# LED-Test-Board_v13.net
KiCad netlist of a schematic drawn in EAGLE
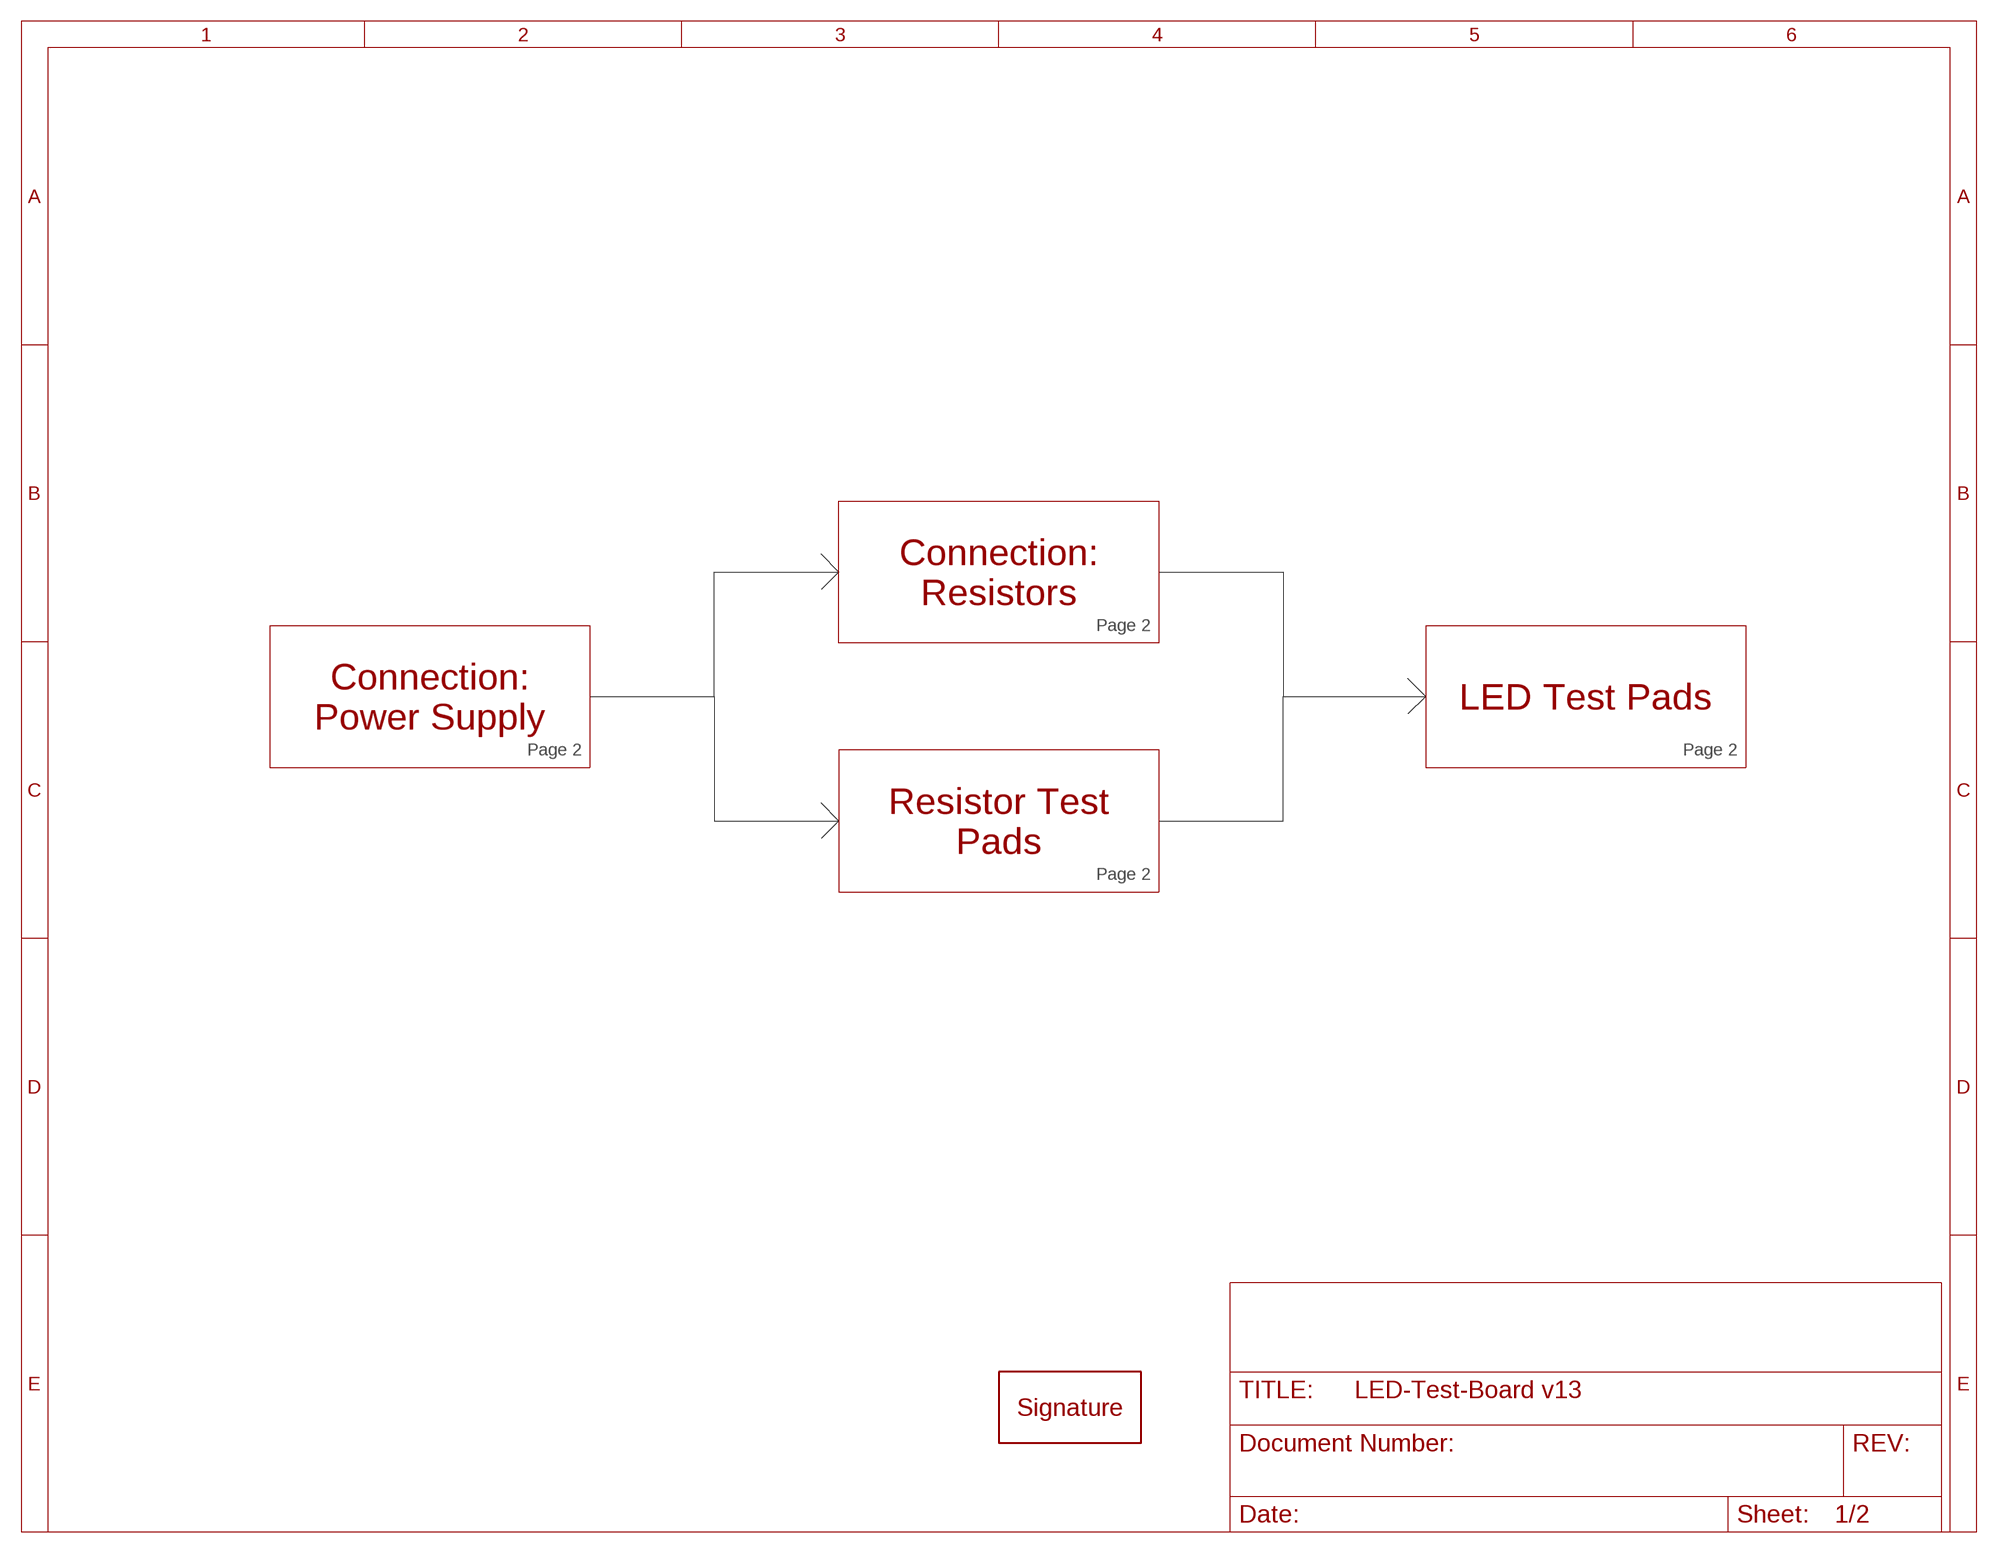
[diagram p0: schematic, sheet 1]
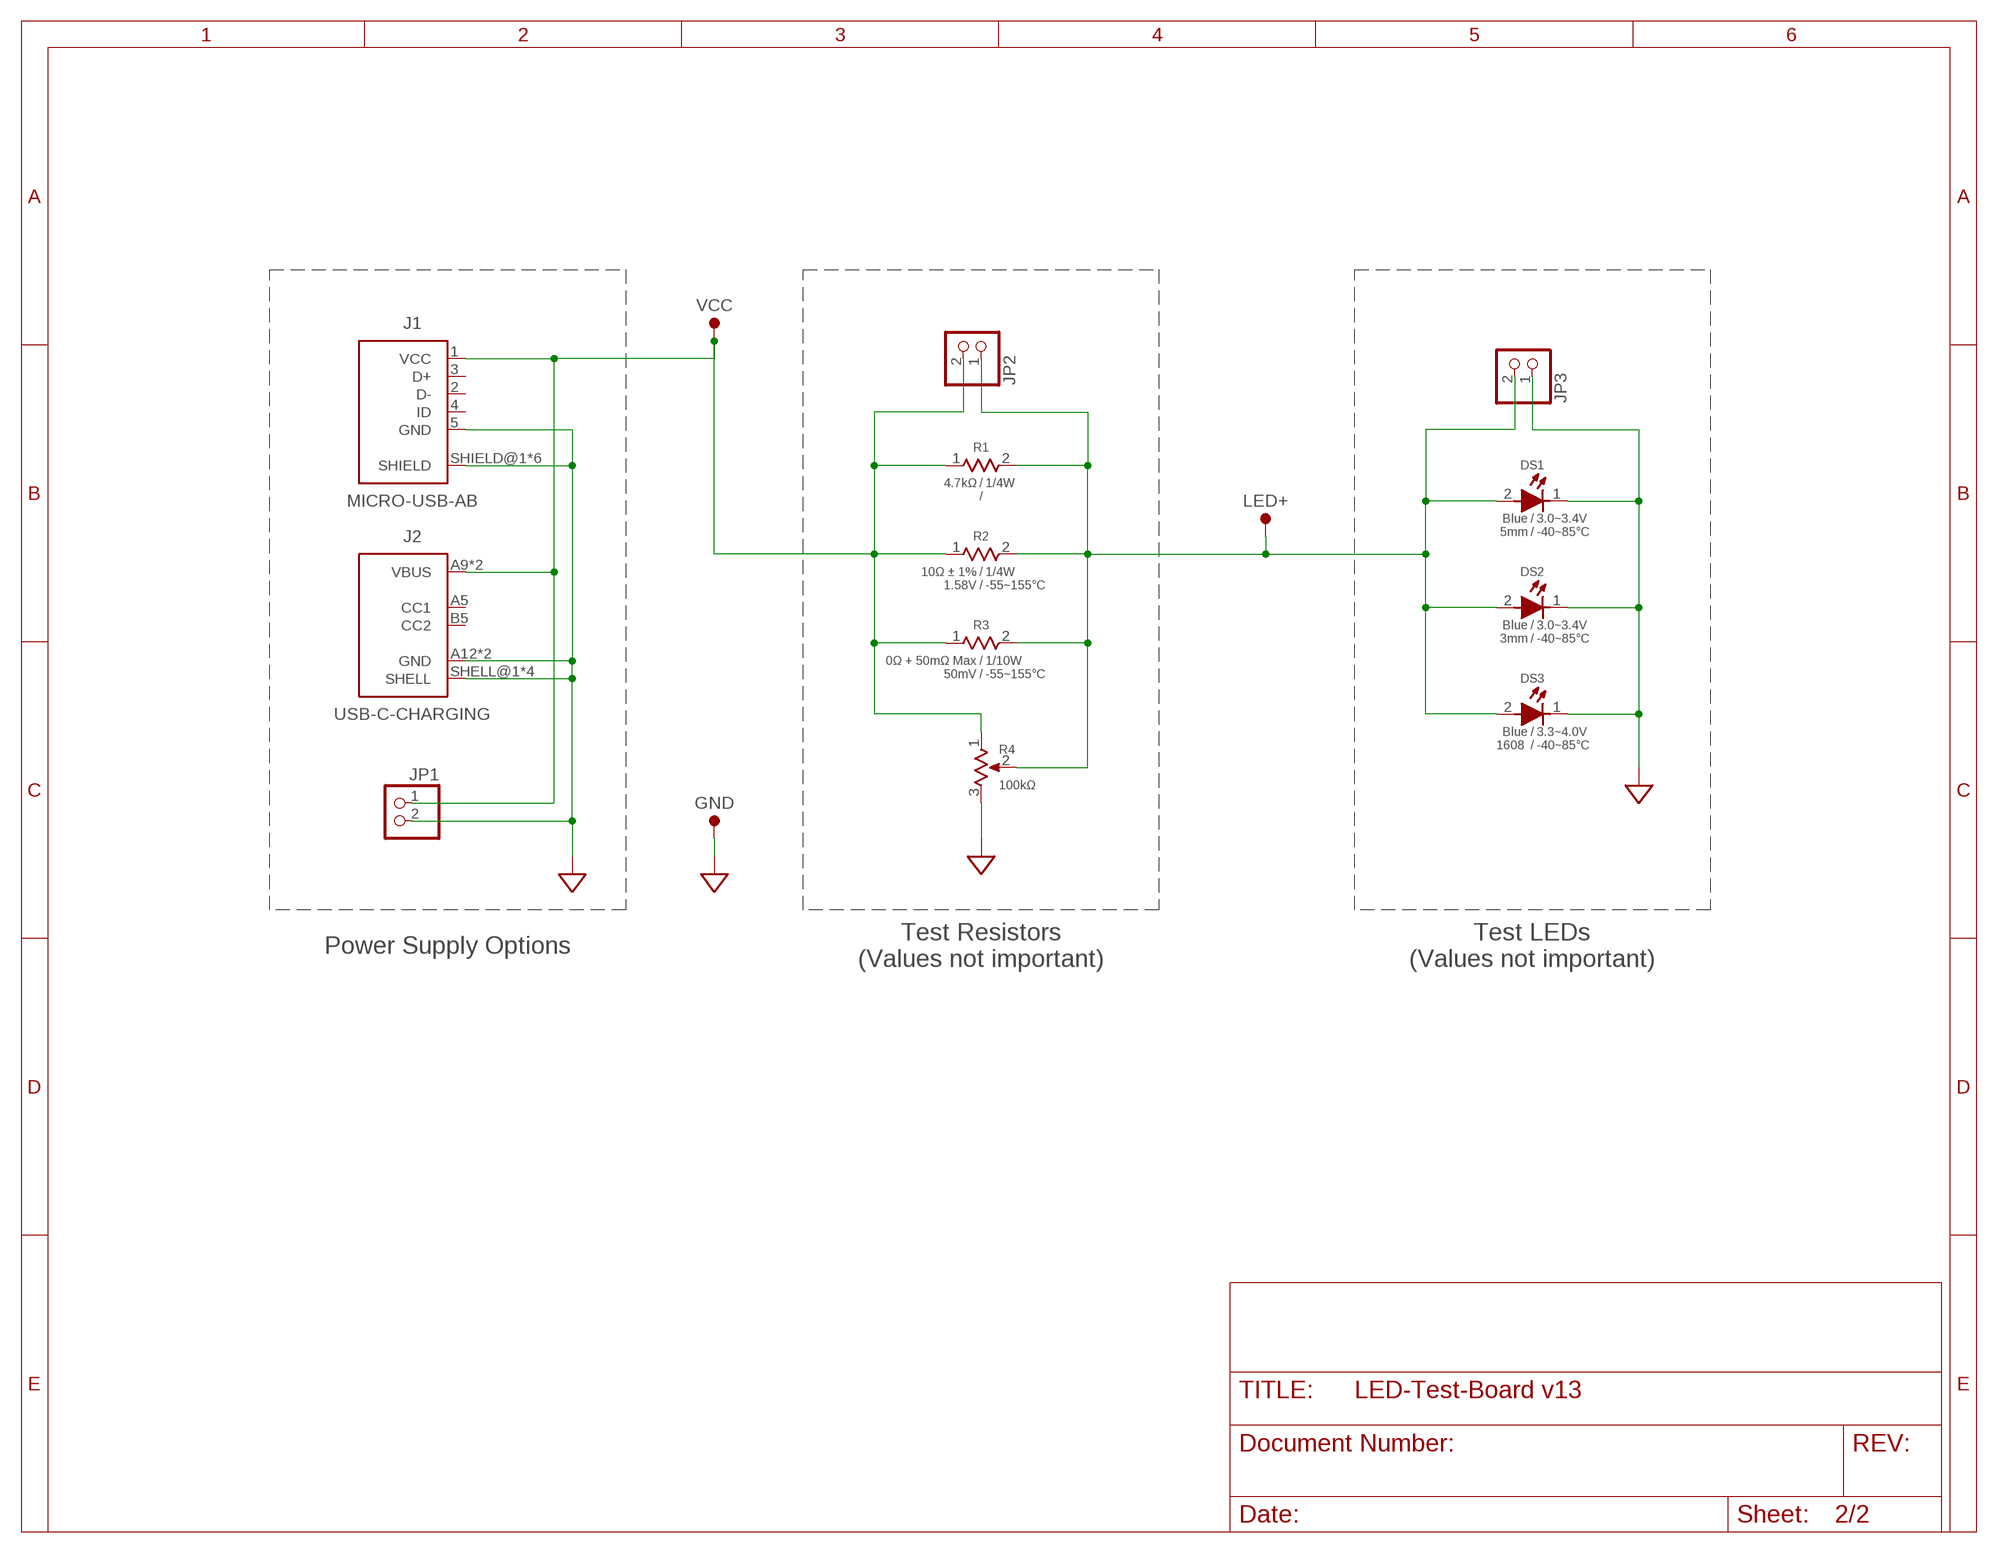
[diagram p1: schematic, sheet 2]

(export (version "E")
  (design (tool "Eeschema 10.0.6"))
  (components
    (comp (ref "DS1")
      (value "Blue")
      (footprint "eagle-import:5MM-TH")
      (fields
        (field (name "SIZE") "5mm")
        (field (name "TEMPERATURE") "-40~85°C")
        (field (name "VOLTAGE") "3.0~3.4V")
      )
      (libsource (lib "eagle-import") (part "LED-H-5MM-TH-BLUE"))
    )
    (comp (ref "DS2")
      (value "Blue")
      (footprint "eagle-import:3MM-TH")
      (fields
        (field (name "SIZE") "3mm")
        (field (name "TEMPERATURE") "-40~85°C")
        (field (name "VOLTAGE") "3.0~3.4V")
      )
      (libsource (lib "eagle-import") (part "LED-H-3MM-TH-BLUE"))
    )
    (comp (ref "DS3")
      (value "Blue")
      (footprint "eagle-import:1608")
      (fields
        (field (name "SIZE") "1608 ")
        (field (name "TEMPERATURE") "-40~85°C")
        (field (name "VOLTAGE") "3.3~4.0V")
      )
      (libsource (lib "eagle-import") (part "LED-H-1608-BLUE"))
    )
    (comp (ref "GND")
      (value "TEST-POINT")
      (footprint "eagle-import:TEST-POINT")
      (libsource (lib "eagle-import") (part "TEST-POINT"))
    )
    (comp (ref "J1")
      (value "MICRO-USB-AB")
      (footprint "eagle-import:47589-0001")
      (libsource (lib "eagle-import") (part "MICRO-USB-AB"))
    )
    (comp (ref "J2")
      (value "USB-C-CHARGING")
      (footprint "eagle-import:USB-4125")
      (libsource (lib "eagle-import") (part "USB-C-CHARGING"))
    )
    (comp (ref "JP1")
      (value "PINHD-1X2")
      (footprint "eagle-import:1X02")
      (libsource (lib "eagle-import") (part "PINHD-1X2"))
    )
    (comp (ref "JP2")
      (value "PINHD-1X2")
      (footprint "eagle-import:1X02")
      (libsource (lib "eagle-import") (part "PINHD-1X2"))
    )
    (comp (ref "JP3")
      (value "PINHD-1X2")
      (footprint "eagle-import:1X02")
      (libsource (lib "eagle-import") (part "PINHD-1X2"))
    )
    (comp (ref "LED+")
      (value "TEST-POINT")
      (footprint "eagle-import:TEST-POINT")
      (libsource (lib "eagle-import") (part "TEST-POINT"))
    )
    (comp (ref "R1")
      (value "4.7kΩ")
      (footprint "eagle-import:1_4W-TH")
      (fields (field (name "POWER") "1/4W"))
      (libsource (lib "eagle-import") (part "RES-H1/4W-TH"))
    )
    (comp (ref "R2")
      (value "10Ω ± 1%")
      (footprint "eagle-import:3216-SEM")
      (fields
        (field (name "POWER") "1/4W")
        (field (name "TEMPERATURE") "-55~155°C")
        (field (name "VOLTAGE") "1.58V")
      )
      (libsource (lib "eagle-import") (part "RES-H-3216-10R"))
    )
    (comp (ref "R3")
      (value "0Ω + 50mΩ Max")
      (footprint "eagle-import:1608-SEM")
      (fields
        (field (name "POWER") "1/10W")
        (field (name "TEMPERATURE") "-55~155°C")
        (field (name "VOLTAGE") "50mV")
      )
      (libsource (lib "eagle-import") (part "RES-H-1608-0R"))
    )
    (comp (ref "R4")
      (value "100kΩ")
      (footprint "eagle-import:3314J")
      (libsource (lib "eagle-import") (part "TRIMPOT-V-100K"))
    )
    (comp (ref "VCC")
      (value "TEST-POINT")
      (footprint "eagle-import:TEST-POINT")
      (libsource (lib "eagle-import") (part "TEST-POINT"))
    )
    (comp (ref "U$5")
      (value "SIGNATURE")
      (footprint "eagle-import:SIGNATURE")
      (libsource (lib "eagle-import") (part "SIGNATURE"))
    )
  )
  (nets
    (net (code "1") (name "GND") (class "Default")
      (node (ref "DS1") (pin "1") (pinfunction "1_1") (pintype "output"))
      (node (ref "DS2") (pin "1") (pinfunction "1_1") (pintype "output"))
      (node (ref "DS3") (pin "1") (pinfunction "1_1") (pintype "output"))
      (node (ref "GND") (pin "TP") (pinfunction "TP_TP") (pintype "bidirectional"))
      (node (ref "J1") (pin "5") (pinfunction "GND_5") (pintype "power_in"))
      (node (ref "J1") (pin "SHIELD@1") (pinfunction "SHIELD_SHIELD@1") (pintype "power_in"))
      (node (ref "J1") (pin "SHIELD@2") (pinfunction "SHIELD_SHIELD@2") (pintype "power_in"))
      (node (ref "J1") (pin "SHIELD@3") (pinfunction "SHIELD_SHIELD@3") (pintype "power_in"))
      (node (ref "J1") (pin "SHIELD@4") (pinfunction "SHIELD_SHIELD@4") (pintype "power_in"))
      (node (ref "J1") (pin "SHIELD@5") (pinfunction "SHIELD_SHIELD@5") (pintype "power_in"))
      (node (ref "J1") (pin "SHIELD@6") (pinfunction "SHIELD_SHIELD@6") (pintype "power_in"))
      (node (ref "J2") (pin "A12") (pinfunction "GND_A12") (pintype "power_in"))
      (node (ref "J2") (pin "B12") (pinfunction "GND_B12") (pintype "power_in"))
      (node (ref "J2") (pin "SHELL@1") (pinfunction "SHELL_SHELL@1") (pintype "power_in"))
      (node (ref "J2") (pin "SHELL@2") (pinfunction "SHELL_SHELL@2") (pintype "power_in"))
      (node (ref "J2") (pin "SHELL@3") (pinfunction "SHELL_SHELL@3") (pintype "power_in"))
      (node (ref "J2") (pin "SHELL@4") (pinfunction "SHELL_SHELL@4") (pintype "power_in"))
      (node (ref "JP1") (pin "2") (pinfunction "2_2") (pintype "passive"))
      (node (ref "JP3") (pin "1") (pinfunction "1_1") (pintype "passive"))
      (node (ref "R4") (pin "3") (pinfunction "3_3") (pintype "passive"))
    )
    (net (code "2") (name "Net-(DS1-Pad2)") (class "Default")
      (node (ref "DS1") (pin "2") (pinfunction "2_2") (pintype "input"))
      (node (ref "DS2") (pin "2") (pinfunction "2_2") (pintype "input"))
      (node (ref "DS3") (pin "2") (pinfunction "2_2") (pintype "input"))
      (node (ref "JP2") (pin "1") (pinfunction "1_1") (pintype "passive"))
      (node (ref "JP3") (pin "2") (pinfunction "2_2") (pintype "passive"))
      (node (ref "LED+") (pin "TP") (pinfunction "TP_TP") (pintype "bidirectional"))
      (node (ref "R1") (pin "2") (pinfunction "2_2") (pintype "passive"))
      (node (ref "R2") (pin "2") (pinfunction "2_2") (pintype "passive"))
      (node (ref "R3") (pin "2") (pinfunction "2_2") (pintype "passive"))
      (node (ref "R4") (pin "2") (pinfunction "2_2") (pintype "passive"))
    )
    (net (code "3") (name "Net-(J1-VCC)") (class "Default")
      (node (ref "J1") (pin "1") (pinfunction "VCC_1") (pintype "power_in"))
      (node (ref "J2") (pin "A9") (pinfunction "VBUS_A9") (pintype "power_in"))
      (node (ref "J2") (pin "B9") (pinfunction "VBUS_B9") (pintype "power_in"))
      (node (ref "JP1") (pin "1") (pinfunction "1_1") (pintype "passive"))
      (node (ref "JP2") (pin "2") (pinfunction "2_2") (pintype "passive"))
      (node (ref "R1") (pin "1") (pinfunction "1_1") (pintype "passive"))
      (node (ref "R2") (pin "1") (pinfunction "1_1") (pintype "passive"))
      (node (ref "R3") (pin "1") (pinfunction "1_1") (pintype "passive"))
      (node (ref "R4") (pin "1") (pinfunction "1_1") (pintype "passive"))
      (node (ref "VCC") (pin "TP") (pinfunction "TP_TP") (pintype "bidirectional"))
    )
    (net (code "4") (name "unconnected-(J1-D+-Pad3)") (class "Default")
      (node (ref "J1") (pin "3") (pinfunction "D+_3") (pintype "input"))
    )
    (net (code "5") (name "unconnected-(J1-D--Pad2)") (class "Default")
      (node (ref "J1") (pin "2") (pinfunction "D-_2") (pintype "output"))
    )
    (net (code "6") (name "unconnected-(J1-ID-Pad4)") (class "Default")
      (node (ref "J1") (pin "4") (pinfunction "ID_4") (pintype "no_connect"))
    )
    (net (code "7") (name "unconnected-(J2-CC1-PadA5)") (class "Default")
      (node (ref "J2") (pin "A5") (pinfunction "CC1_A5") (pintype "bidirectional"))
    )
    (net (code "8") (name "unconnected-(J2-CC2-PadB5)") (class "Default")
      (node (ref "J2") (pin "B5") (pinfunction "CC2_B5") (pintype "bidirectional"))
    )
  )
)
